# PCB_Gabri1_1.net
KiCad netlist of a schematic drawn in EAGLE
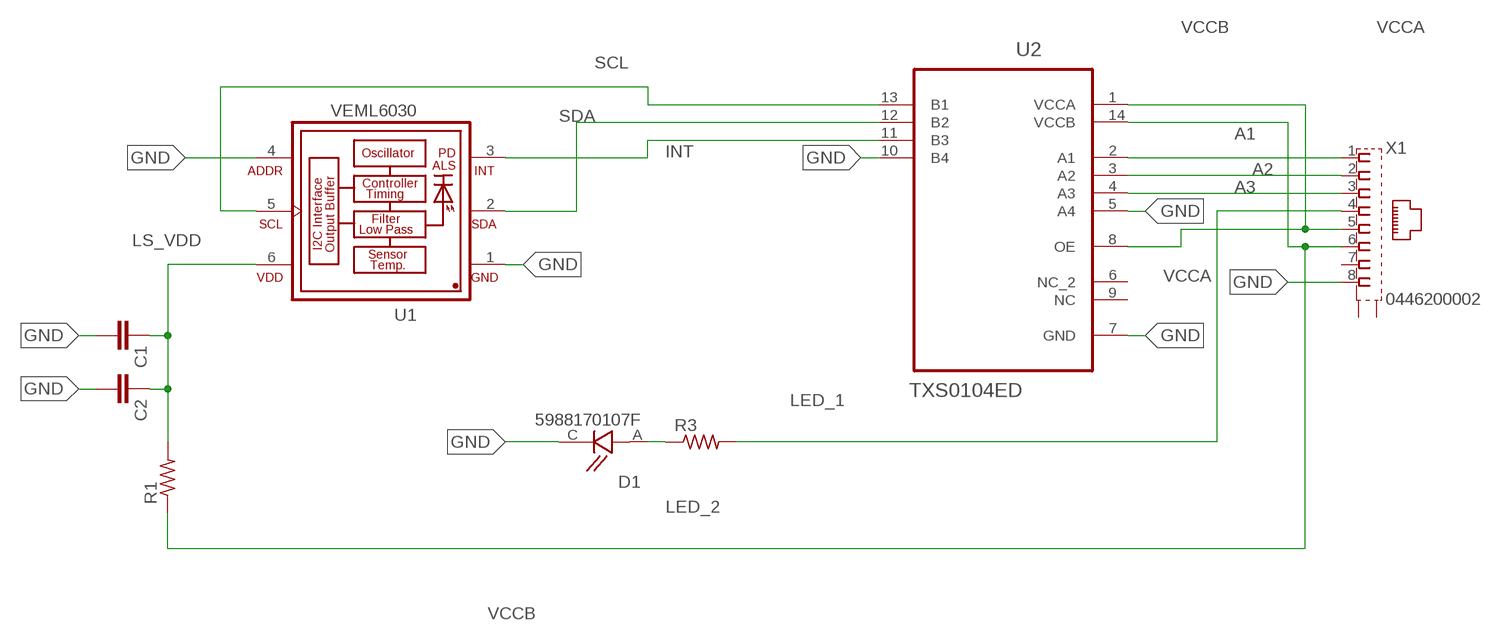
[diagram p0: schematic, sheet 1]

(export (version "E")
  (design (tool "Eeschema 10.0.6"))
  (components
    (comp (ref "C1")
      (value "C-EU025-024X044")
      (footprint "eagle-import:C025-024X044")
      (libsource (lib "eagle-import") (part "C-EU025-024X044"))
    )
    (comp (ref "C2")
      (value "C-EU025-024X044")
      (footprint "eagle-import:C025-024X044")
      (libsource (lib "eagle-import") (part "C-EU025-024X044"))
    )
    (comp (ref "D1")
      (value "5988170107F")
      (footprint "eagle-import:LEDC2012X70N")
      (fields (field (name "MF") "Dialight"))
      (libsource (lib "eagle-import") (part "5988170107F"))
    )
    (comp (ref "R1")
      (value "R-US_R0805")
      (footprint "eagle-import:R0805")
      (libsource (lib "eagle-import") (part "R-US_R0805"))
    )
    (comp (ref "R3")
      (value "R-US_R0805")
      (footprint "eagle-import:R0805")
      (libsource (lib "eagle-import") (part "R-US_R0805"))
    )
    (comp (ref "U1")
      (value "VEML6030")
      (footprint "eagle-import:VISHAY_VEML6030_2X2X0.87")
      (fields (field (name "MF") "Vishay"))
      (libsource (lib "eagle-import") (part "VEML6030"))
    )
    (comp (ref "U2")
      (value "TXS0104ED")
      (footprint "eagle-import:SOIC127P600X175-14N")
      (fields (field (name "MF") "Texas Instruments"))
      (libsource (lib "eagle-import") (part "TXS0104ED"))
    )
    (comp (ref "X1")
      (value "0446200002")
      (footprint "eagle-import:0446200002")
      (fields (field (name "MF") "Molex, LLC"))
      (libsource (lib "eagle-import") (part "0446200002"))
    )
  )
  (nets
    (net (code "1") (name "/A1") (class "Default")
      (node (ref "U2") (pin "2") (pinfunction "A1_2") (pintype "input"))
      (node (ref "X1") (pin "1") (pinfunction "1_1") (pintype "passive"))
    )
    (net (code "2") (name "/A2") (class "Default")
      (node (ref "U2") (pin "3") (pinfunction "A2_3") (pintype "input"))
      (node (ref "X1") (pin "2") (pinfunction "2_2") (pintype "passive"))
    )
    (net (code "3") (name "/A3") (class "Default")
      (node (ref "U2") (pin "4") (pinfunction "A3_4") (pintype "input"))
      (node (ref "X1") (pin "3") (pinfunction "3_3") (pintype "passive"))
    )
    (net (code "4") (name "/INT") (class "Default")
      (node (ref "U1") (pin "3") (pinfunction "INT_3") (pintype "output"))
      (node (ref "U2") (pin "11") (pinfunction "B3_11") (pintype "output"))
    )
    (net (code "5") (name "/LED_1") (class "Default")
      (node (ref "R3") (pin "2") (pinfunction "2_2") (pintype "passive"))
      (node (ref "X1") (pin "4") (pinfunction "4_4") (pintype "passive"))
    )
    (net (code "6") (name "/LED_2") (class "Default")
      (node (ref "D1") (pin "A") (pinfunction "A_A") (pintype "passive"))
      (node (ref "R3") (pin "1") (pinfunction "1_1") (pintype "passive"))
    )
    (net (code "7") (name "/LS_VDD") (class "Default")
      (node (ref "C1") (pin "1") (pinfunction "1_1") (pintype "passive"))
      (node (ref "C2") (pin "1") (pinfunction "1_1") (pintype "passive"))
      (node (ref "R1") (pin "2") (pinfunction "2_2") (pintype "passive"))
      (node (ref "U1") (pin "6") (pinfunction "VDD_6") (pintype "power_in"))
    )
    (net (code "8") (name "/SCL") (class "Default")
      (node (ref "U1") (pin "5") (pinfunction "SCL_5") (pintype "input"))
      (node (ref "U2") (pin "13") (pinfunction "B1_13") (pintype "output"))
    )
    (net (code "9") (name "/SDA") (class "Default")
      (node (ref "U1") (pin "2") (pinfunction "SDA_2") (pintype "bidirectional"))
      (node (ref "U2") (pin "12") (pinfunction "B2_12") (pintype "output"))
    )
    (net (code "10") (name "/VCCA") (class "Default")
      (node (ref "U2") (pin "1") (pinfunction "VCCA_1") (pintype "power_in"))
      (node (ref "U2") (pin "8") (pinfunction "OE_8") (pintype "input"))
      (node (ref "X1") (pin "5") (pinfunction "5_5") (pintype "passive"))
    )
    (net (code "11") (name "/VCCB") (class "Default")
      (node (ref "R1") (pin "1") (pinfunction "1_1") (pintype "passive"))
      (node (ref "U2") (pin "14") (pinfunction "VCCB_14") (pintype "power_in"))
      (node (ref "X1") (pin "6") (pinfunction "6_6") (pintype "passive"))
    )
    (net (code "12") (name "GND") (class "Default")
      (node (ref "C1") (pin "2") (pinfunction "2_2") (pintype "passive"))
      (node (ref "C2") (pin "2") (pinfunction "2_2") (pintype "passive"))
      (node (ref "D1") (pin "C") (pinfunction "C_C") (pintype "passive"))
      (node (ref "U1") (pin "1") (pinfunction "GND_1") (pintype "power_in"))
      (node (ref "U1") (pin "4") (pinfunction "ADDR_4") (pintype "bidirectional"))
      (node (ref "U2") (pin "10") (pinfunction "B4_10") (pintype "output"))
      (node (ref "U2") (pin "5") (pinfunction "A4_5") (pintype "input"))
      (node (ref "U2") (pin "7") (pinfunction "GND_7") (pintype "passive"))
      (node (ref "X1") (pin "8") (pinfunction "8_8") (pintype "passive"))
    )
    (net (code "13") (name "unconnected-(U2-NC-Pad9)") (class "Default")
      (node (ref "U2") (pin "9") (pinfunction "NC_9") (pintype "no_connect"))
    )
    (net (code "14") (name "unconnected-(U2-NC_2-Pad6)") (class "Default")
      (node (ref "U2") (pin "6") (pinfunction "NC_2_6") (pintype "no_connect"))
    )
    (net (code "15") (name "unconnected-(X1-Pad7)") (class "Default")
      (node (ref "X1") (pin "7") (pinfunction "7_7") (pintype "passive"))
    )
    (net (code "16") (name "unconnected-(X1-S1-PadS@1)") (class "Default")
      (node (ref "X1") (pin "S@1") (pinfunction "S1_S@1") (pintype "passive"))
    )
    (net (code "17") (name "unconnected-(X1-S2-PadS@2)") (class "Default")
      (node (ref "X1") (pin "S@2") (pinfunction "S2_S@2") (pintype "passive"))
    )
  )
)
